# DAQmx.net
KiCad netlist of a schematic drawn in Altium Designer
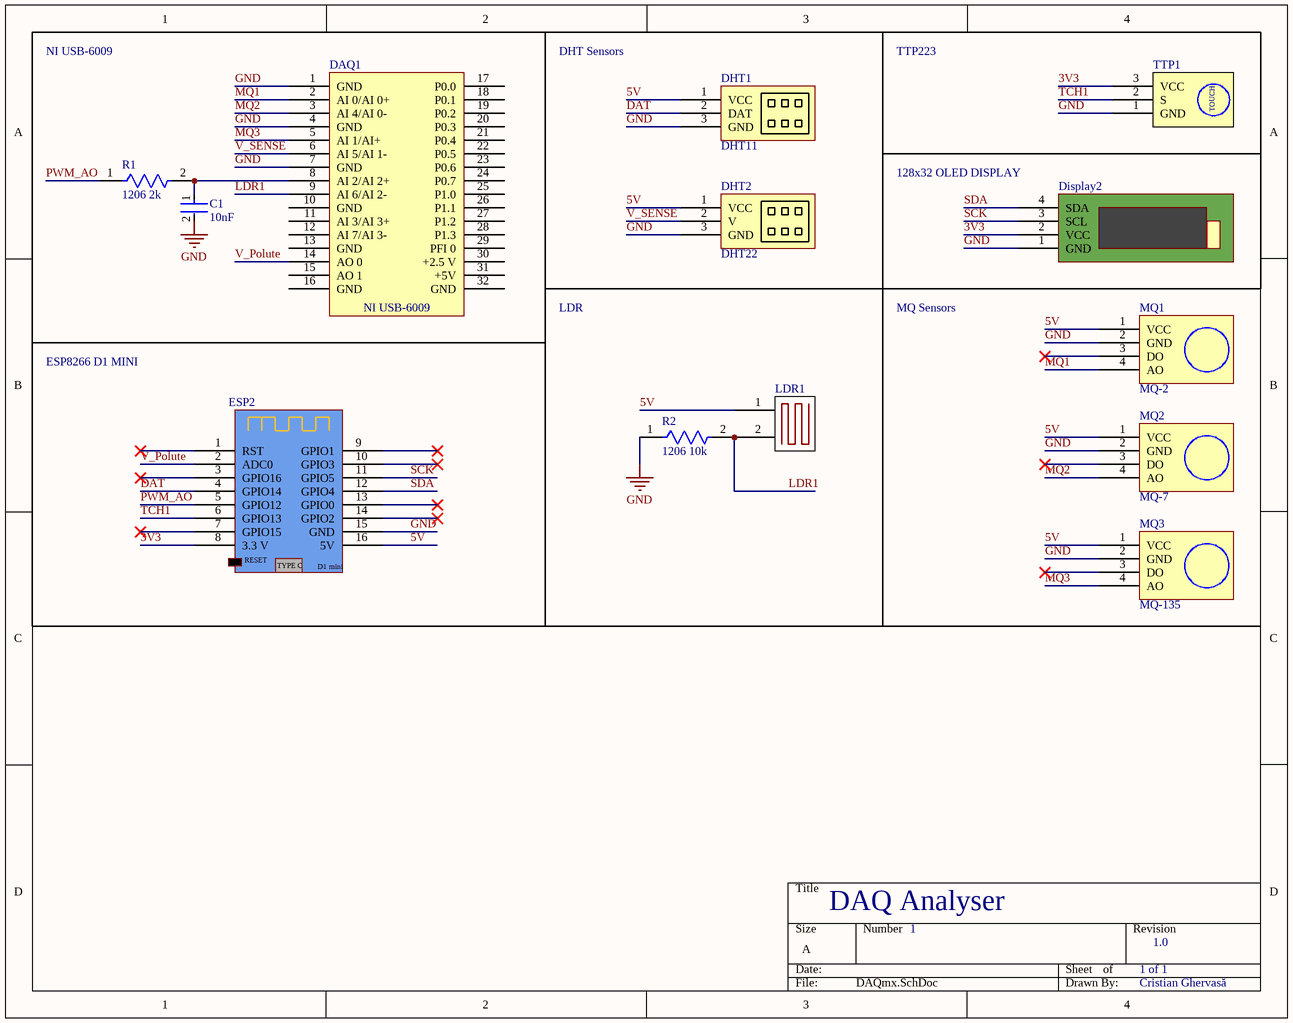
[diagram p0: DAQmx.SchDoc]

(export (version "E")
  (design (tool "Eeschema 10.0.6"))
  (components
    (comp (ref "C1")
      (value "10nF")
      (footprint "FP-C1206C-EB-MFG")
      (description "C1206 10,000 pF C0G 5.00% 50 V")
      (fields
        (field (name "MANUFACTURER") "KEMET")
        (field (name "OCTOPART") "https://octopart.com/c1206c103j5gacauto-kemet-88376196")
      )
      (libsource (lib "Altium Content Vault") (part "b4654b650e69147ec39a6b967a45e02"))
    )
    (comp (ref "DAQ1")
      (value "NI USB-6009")
      (footprint "NI USB-6009")
      (libsource (lib "IoT") (part "NI USB-6009"))
    )
    (comp (ref "DHT1") (value "DHT11") (footprint "DHT22") (libsource (lib "IoT") (part "DHT11")))
    (comp (ref "DHT2") (value "DHT22") (footprint "DHT22") (libsource (lib "IoT") (part "DHT22")))
    (comp (ref "Display2")
      (value "128x32 OLED DISPLAY")
      (footprint "128x32 OLED Display")
      (libsource (lib "IoT") (part "128x32 OLED DISPLAY"))
    )
    (comp (ref "ESP2")
      (value "ESP8266 D1 MINI")
      (footprint "ESP8266 D1 Mini")
      (libsource (lib "IoT") (part "ESP8266 D1 MINI"))
    )
    (comp (ref "LDR1") (value "LDR") (footprint "LDR") (libsource (lib "IoT") (part "LDR")))
    (comp (ref "MQ1") (value "MQ-2") (footprint "MQ-135") (libsource (lib "IoT") (part "MQ-2")))
    (comp (ref "MQ2") (value "MQ-7") (footprint "MQ-135") (libsource (lib "IoT") (part "MQ-7")))
    (comp (ref "MQ3") (value "MQ-135") (footprint "MQ-135") (libsource (lib "IoT") (part "MQ-135")))
    (comp (ref "R1")
      (value "1206 2k")
      (footprint "FP-TFCR1206-IPC_B")
      (description "RES Thin Film, 2kΩ, 0.1%, 0.25W, 25ppm/°C, 1206")
      (libsource (lib "Altium Content Vault") (part "1029c3af85768c4190bb7ad29bc67b5"))
    )
    (comp (ref "R2")
      (value "1206 10k")
      (footprint "FP-CRGCQ1206-IPC_C")
      (description "CRGCQ1206 10KΩ 0.25W 1% ±100ppm/°C 200V")
      (fields (field (name "MANUFACTURER") "TE Connectivity") (field (name "TOLERANCE") "0.01"))
      (libsource (lib "Altium Content Vault") (part "1029c3af85768c4190bb7ad29bc67b5"))
    )
    (comp (ref "TTP1") (value "TTP223") (footprint "TTP223") (libsource (lib "IoT") (part "TTP223")))
  )
  (nets
    (net (code "1") (name "/3V3") (class "Default")
      (node (ref "Display2") (pin "2") (pinfunction "VCC_2") (pintype "passive"))
      (node (ref "ESP2") (pin "8") (pinfunction "3.3_V_8") (pintype "passive"))
      (node (ref "TTP1") (pin "3") (pinfunction "VCC_3") (pintype "passive"))
    )
    (net (code "2") (name "/5V") (class "Default")
      (node (ref "DHT1") (pin "1") (pinfunction "VCC_1") (pintype "passive"))
      (node (ref "DHT2") (pin "1") (pinfunction "VCC_1") (pintype "passive"))
      (node (ref "ESP2") (pin "16") (pinfunction "5V_16") (pintype "passive"))
      (node (ref "LDR1") (pin "1") (pintype "passive"))
      (node (ref "MQ1") (pin "1") (pinfunction "VCC_1") (pintype "passive"))
      (node (ref "MQ2") (pin "1") (pinfunction "VCC_1") (pintype "passive"))
      (node (ref "MQ3") (pin "1") (pinfunction "VCC_1") (pintype "passive"))
    )
    (net (code "3") (name "/DAT") (class "Default")
      (node (ref "DHT1") (pin "2") (pinfunction "DAT_2") (pintype "passive"))
      (node (ref "ESP2") (pin "4") (pinfunction "GPIO14_4") (pintype "passive"))
    )
    (net (code "4") (name "/LDR1") (class "Default")
      (node (ref "DAQ1") (pin "9") (pinfunction "AI_6/AI_2-_9") (pintype "passive"))
      (node (ref "LDR1") (pin "2") (pintype "passive"))
      (node (ref "R2") (pin "2") (pinfunction "2_2") (pintype "passive"))
    )
    (net (code "5") (name "/MQ1") (class "Default")
      (node (ref "DAQ1") (pin "2") (pinfunction "AI_0/AI_0+_2") (pintype "passive"))
      (node (ref "MQ1") (pin "4") (pinfunction "AO_4") (pintype "passive"))
    )
    (net (code "6") (name "/MQ2") (class "Default")
      (node (ref "DAQ1") (pin "3") (pinfunction "AI_4/AI_0-_3") (pintype "passive"))
      (node (ref "MQ2") (pin "4") (pinfunction "AO_4") (pintype "passive"))
    )
    (net (code "7") (name "/MQ3") (class "Default")
      (node (ref "DAQ1") (pin "5") (pinfunction "AI_1/AI+_5") (pintype "passive"))
      (node (ref "MQ3") (pin "4") (pinfunction "AO_4") (pintype "passive"))
    )
    (net (code "8") (name "/PWM_AO") (class "Default")
      (node (ref "ESP2") (pin "5") (pinfunction "GPIO12_5") (pintype "passive"))
      (node (ref "R1") (pin "1") (pinfunction "1_1") (pintype "passive"))
    )
    (net (code "9") (name "/SCK") (class "Default")
      (node (ref "Display2") (pin "3") (pinfunction "SCL_3") (pintype "passive"))
      (node (ref "ESP2") (pin "11") (pinfunction "GPIO5_11") (pintype "passive"))
    )
    (net (code "10") (name "/SDA") (class "Default")
      (node (ref "Display2") (pin "4") (pinfunction "SDA_4") (pintype "passive"))
      (node (ref "ESP2") (pin "12") (pinfunction "GPIO4_12") (pintype "passive"))
    )
    (net (code "11") (name "/TCH1") (class "Default")
      (node (ref "ESP2") (pin "6") (pinfunction "GPIO13_6") (pintype "passive"))
      (node (ref "TTP1") (pin "2") (pinfunction "S_2") (pintype "passive"))
    )
    (net (code "12") (name "/V_Polute") (class "Default")
      (node (ref "DAQ1") (pin "14") (pinfunction "AO_0_14") (pintype "passive"))
      (node (ref "ESP2") (pin "2") (pinfunction "ADC0_2") (pintype "passive"))
    )
    (net (code "13") (name "/V_SENSE") (class "Default")
      (node (ref "DAQ1") (pin "6") (pinfunction "AI_5/AI_1-_6") (pintype "passive"))
      (node (ref "DHT2") (pin "2") (pinfunction "V_2") (pintype "passive"))
    )
    (net (code "14") (name "GND") (class "Default")
      (node (ref "C1") (pin "2") (pinfunction "2_2") (pintype "passive"))
      (node (ref "DAQ1") (pin "1") (pinfunction "GND_1") (pintype "passive"))
      (node (ref "DAQ1") (pin "4") (pinfunction "GND_4") (pintype "passive"))
      (node (ref "DAQ1") (pin "7") (pinfunction "GND_7") (pintype "passive"))
      (node (ref "DHT1") (pin "3") (pinfunction "GND_3") (pintype "passive"))
      (node (ref "DHT2") (pin "3") (pinfunction "GND_3") (pintype "passive"))
      (node (ref "Display2") (pin "1") (pinfunction "GND_1") (pintype "passive"))
      (node (ref "ESP2") (pin "15") (pinfunction "GND_15") (pintype "passive"))
      (node (ref "MQ1") (pin "2") (pinfunction "GND_2") (pintype "passive"))
      (node (ref "MQ2") (pin "2") (pinfunction "GND_2") (pintype "passive"))
      (node (ref "MQ3") (pin "2") (pinfunction "GND_2") (pintype "passive"))
      (node (ref "R2") (pin "1") (pinfunction "1_1") (pintype "passive"))
      (node (ref "TTP1") (pin "1") (pinfunction "GND_1") (pintype "passive"))
    )
    (net (code "15") (name "Net-(DAQ1-AI_2{slash}AI_2+)") (class "Default")
      (node (ref "C1") (pin "1") (pinfunction "1_1") (pintype "passive"))
      (node (ref "DAQ1") (pin "8") (pinfunction "AI_2/AI_2+_8") (pintype "passive"))
      (node (ref "R1") (pin "2") (pinfunction "2_2") (pintype "passive"))
    )
    (net (code "16") (name "unconnected-(DAQ1-+2.5_V-Pad30)") (class "Default")
      (node (ref "DAQ1") (pin "30") (pinfunction "+2.5_V_30") (pintype "passive"))
    )
    (net (code "17") (name "unconnected-(DAQ1-+5V-Pad31)") (class "Default")
      (node (ref "DAQ1") (pin "31") (pinfunction "+5V_31") (pintype "passive"))
    )
    (net (code "18") (name "unconnected-(DAQ1-AI_3{slash}AI_3+-Pad11)") (class "Default")
      (node (ref "DAQ1") (pin "11") (pinfunction "AI_3/AI_3+_11") (pintype "passive"))
    )
    (net (code "19") (name "unconnected-(DAQ1-AI_7{slash}AI_3--Pad12)") (class "Default")
      (node (ref "DAQ1") (pin "12") (pinfunction "AI_7/AI_3-_12") (pintype "passive"))
    )
    (net (code "20") (name "unconnected-(DAQ1-AO_1-Pad15)") (class "Default")
      (node (ref "DAQ1") (pin "15") (pinfunction "AO_1_15") (pintype "passive"))
    )
    (net (code "21") (name "unconnected-(DAQ1-GND-Pad10)") (class "Default")
      (node (ref "DAQ1") (pin "10") (pinfunction "GND_10") (pintype "passive"))
    )
    (net (code "22") (name "unconnected-(DAQ1-GND-Pad13)") (class "Default")
      (node (ref "DAQ1") (pin "13") (pinfunction "GND_13") (pintype "passive"))
    )
    (net (code "23") (name "unconnected-(DAQ1-GND-Pad16)") (class "Default")
      (node (ref "DAQ1") (pin "16") (pinfunction "GND_16") (pintype "passive"))
    )
    (net (code "24") (name "unconnected-(DAQ1-GND-Pad32)") (class "Default")
      (node (ref "DAQ1") (pin "32") (pinfunction "GND_32") (pintype "passive"))
    )
    (net (code "25") (name "unconnected-(DAQ1-P0.0-Pad17)") (class "Default")
      (node (ref "DAQ1") (pin "17") (pinfunction "P0.0_17") (pintype "passive"))
    )
    (net (code "26") (name "unconnected-(DAQ1-P0.1-Pad18)") (class "Default")
      (node (ref "DAQ1") (pin "18") (pinfunction "P0.1_18") (pintype "passive"))
    )
    (net (code "27") (name "unconnected-(DAQ1-P0.2-Pad19)") (class "Default")
      (node (ref "DAQ1") (pin "19") (pinfunction "P0.2_19") (pintype "passive"))
    )
    (net (code "28") (name "unconnected-(DAQ1-P0.3-Pad20)") (class "Default")
      (node (ref "DAQ1") (pin "20") (pinfunction "P0.3_20") (pintype "passive"))
    )
    (net (code "29") (name "unconnected-(DAQ1-P0.4-Pad21)") (class "Default")
      (node (ref "DAQ1") (pin "21") (pinfunction "P0.4_21") (pintype "passive"))
    )
    (net (code "30") (name "unconnected-(DAQ1-P0.5-Pad22)") (class "Default")
      (node (ref "DAQ1") (pin "22") (pinfunction "P0.5_22") (pintype "passive"))
    )
    (net (code "31") (name "unconnected-(DAQ1-P0.6-Pad23)") (class "Default")
      (node (ref "DAQ1") (pin "23") (pinfunction "P0.6_23") (pintype "passive"))
    )
    (net (code "32") (name "unconnected-(DAQ1-P0.7-Pad24)") (class "Default")
      (node (ref "DAQ1") (pin "24") (pinfunction "P0.7_24") (pintype "passive"))
    )
    (net (code "33") (name "unconnected-(DAQ1-P1.0-Pad25)") (class "Default")
      (node (ref "DAQ1") (pin "25") (pinfunction "P1.0_25") (pintype "passive"))
    )
    (net (code "34") (name "unconnected-(DAQ1-P1.1-Pad26)") (class "Default")
      (node (ref "DAQ1") (pin "26") (pinfunction "P1.1_26") (pintype "passive"))
    )
    (net (code "35") (name "unconnected-(DAQ1-P1.2-Pad27)") (class "Default")
      (node (ref "DAQ1") (pin "27") (pinfunction "P1.2_27") (pintype "passive"))
    )
    (net (code "36") (name "unconnected-(DAQ1-P1.3-Pad28)") (class "Default")
      (node (ref "DAQ1") (pin "28") (pinfunction "P1.3_28") (pintype "passive"))
    )
    (net (code "37") (name "unconnected-(DAQ1-PFI_0-Pad29)") (class "Default")
      (node (ref "DAQ1") (pin "29") (pinfunction "PFI_0_29") (pintype "passive"))
    )
    (net (code "38") (name "unconnected-(ESP2-GPIO0-Pad13)") (class "Default")
      (node (ref "ESP2") (pin "13") (pinfunction "GPIO0_13") (pintype "passive+no_connect"))
    )
    (net (code "39") (name "unconnected-(ESP2-GPIO1-Pad9)") (class "Default")
      (node (ref "ESP2") (pin "9") (pinfunction "GPIO1_9") (pintype "passive+no_connect"))
    )
    (net (code "40") (name "unconnected-(ESP2-GPIO2-Pad14)") (class "Default")
      (node (ref "ESP2") (pin "14") (pinfunction "GPIO2_14") (pintype "passive+no_connect"))
    )
    (net (code "41") (name "unconnected-(ESP2-GPIO3-Pad10)") (class "Default")
      (node (ref "ESP2") (pin "10") (pinfunction "GPIO3_10") (pintype "passive+no_connect"))
    )
    (net (code "42") (name "unconnected-(ESP2-GPIO15-Pad7)") (class "Default")
      (node (ref "ESP2") (pin "7") (pinfunction "GPIO15_7") (pintype "passive+no_connect"))
    )
    (net (code "43") (name "unconnected-(ESP2-GPIO16-Pad3)") (class "Default")
      (node (ref "ESP2") (pin "3") (pinfunction "GPIO16_3") (pintype "passive+no_connect"))
    )
    (net (code "44") (name "unconnected-(ESP2-RST-Pad1)") (class "Default")
      (node (ref "ESP2") (pin "1") (pinfunction "RST_1") (pintype "passive+no_connect"))
    )
    (net (code "45") (name "unconnected-(MQ1-DO-Pad3)") (class "Default")
      (node (ref "MQ1") (pin "3") (pinfunction "DO_3") (pintype "passive+no_connect"))
    )
    (net (code "46") (name "unconnected-(MQ2-DO-Pad3)") (class "Default")
      (node (ref "MQ2") (pin "3") (pinfunction "DO_3") (pintype "passive+no_connect"))
    )
    (net (code "47") (name "unconnected-(MQ3-DO-Pad3)") (class "Default")
      (node (ref "MQ3") (pin "3") (pinfunction "DO_3") (pintype "passive+no_connect"))
    )
  )
)
